# LORATA.net
KiCad netlist of a schematic drawn in Altium Designer
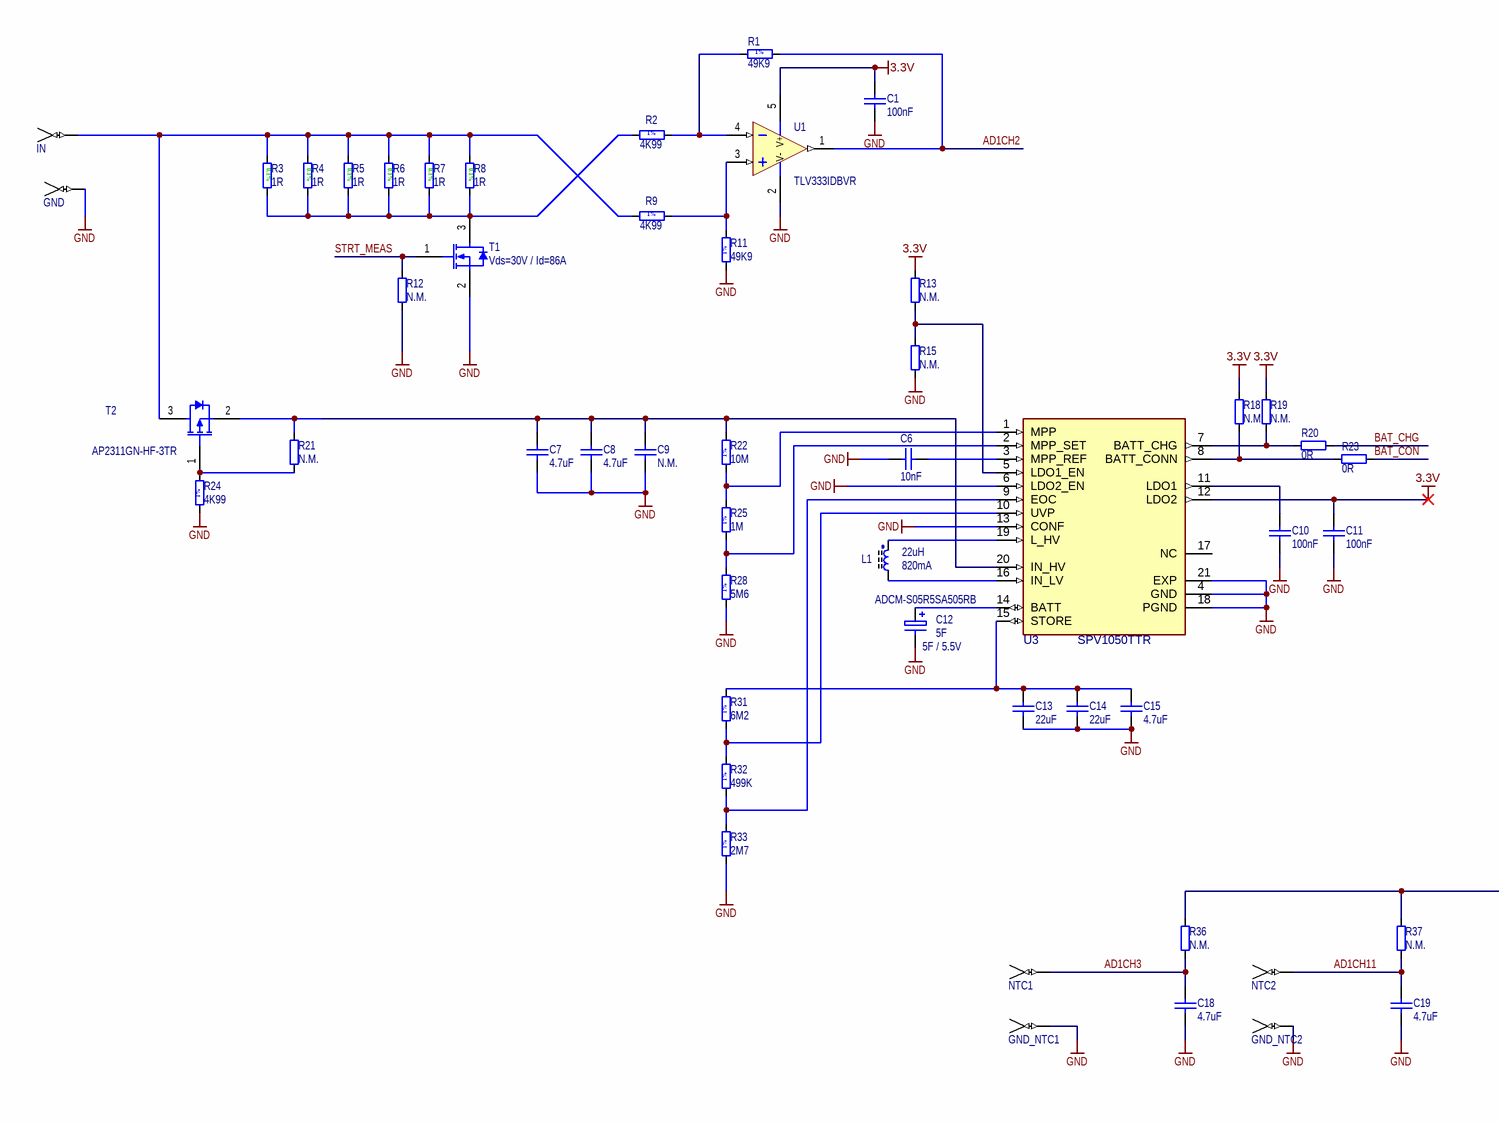
[diagram p0: LORATA.SchDoc, left]
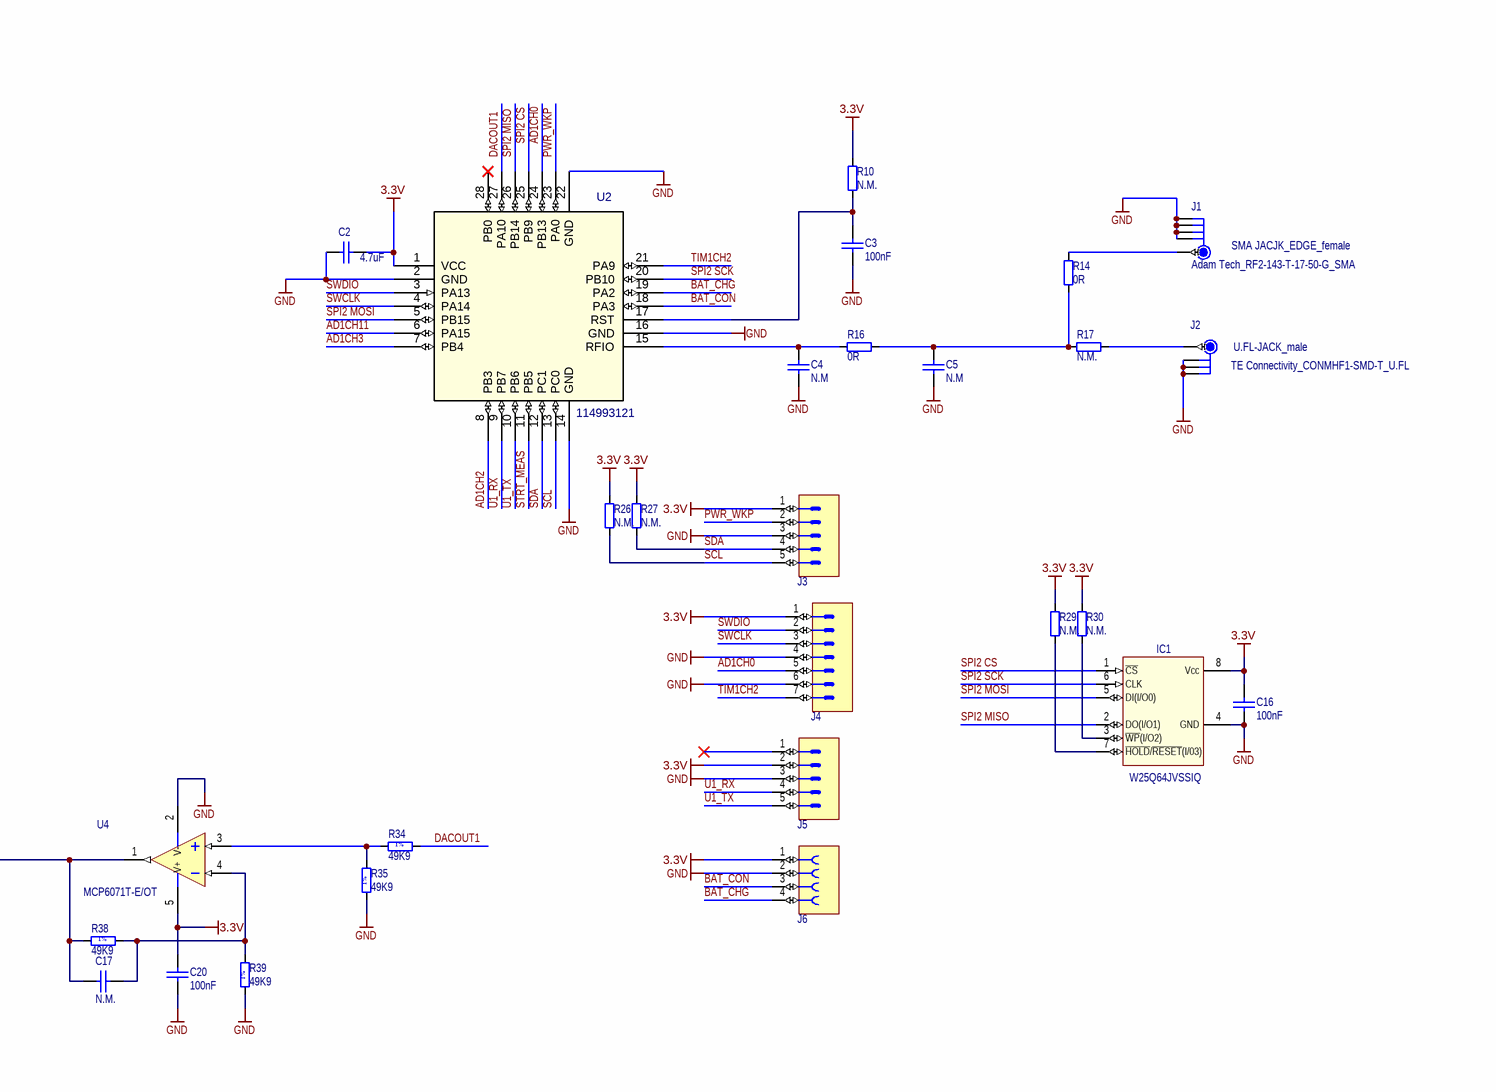
[diagram p1: LORATA.SchDoc, right]

(export (version "E")
  (design (tool "Eeschema 10.0.6"))
  (components
    (comp (ref "C1")
      (value "100nF")
      (footprint "CAPC1608N")
      (description "Non-polarised capacitor")
      (fields
        (field (name "PART NUMBER") "CC0603_100NF_50V_10%_X7R")
        (field (name "VOLTAGE") "50V")
        (field (name "AUTHOR") "V.Shishkov")
      )
      (libsource (lib "IDT_BASE") (part "C"))
    )
    (comp (ref "C2")
      (value "4.7uF")
      (footprint "CAPC3216N")
      (description "Non-polarised capacitor")
      (fields
        (field (name "PART NUMBER") "CC1206_4.7UF_50V_10%_X7R")
        (field (name "VOLTAGE") "50V")
        (field (name "AUTHOR") "V.Shishkov")
      )
      (libsource (lib "IDT_BASE") (part "C"))
    )
    (comp (ref "C3")
      (value "100nF")
      (footprint "CAPC1608N")
      (description "Non-polarised capacitor")
      (fields
        (field (name "PART NUMBER") "CC0603_100NF_50V_10%_X7R")
        (field (name "VOLTAGE") "50V")
        (field (name "AUTHOR") "V.Shishkov")
      )
      (libsource (lib "IDT_BASE") (part "C"))
    )
    (comp (ref "C4")
      (value "N.M")
      (footprint "CAPC1608N")
      (description "Non-polarised capacitor")
      (fields
        (field (name "PART NUMBER") "CC0603_NO-VALUE")
        (field (name "MANUFACTURER") "GENERIC")
        (field (name "AUTHOR") "L.K")
      )
      (libsource (lib "IDT_BASE") (part "C"))
    )
    (comp (ref "C5")
      (value "N.M")
      (footprint "CAPC1608N")
      (description "Non-polarised capacitor")
      (fields
        (field (name "PART NUMBER") "CC0603_NO-VALUE")
        (field (name "MANUFACTURER") "GENERIC")
        (field (name "AUTHOR") "L.K")
      )
      (libsource (lib "IDT_BASE") (part "C"))
    )
    (comp (ref "C6")
      (value "10nF")
      (footprint "CAPC1608N")
      (description "Non-polarised capacitor")
      (fields
        (field (name "PART NUMBER") "CC0603_10NF_50V_10%_X7R")
        (field (name "VOLTAGE") "50V")
        (field (name "AUTHOR") "V.Shishkov")
      )
      (libsource (lib "IDT_BASE") (part "C"))
    )
    (comp (ref "C7")
      (value "4.7uF")
      (footprint "CAPC3216N")
      (description "Non-polarised capacitor")
      (fields
        (field (name "PART NUMBER") "CC1206_4.7UF_50V_10%_X7R")
        (field (name "VOLTAGE") "50V")
        (field (name "AUTHOR") "V.Shishkov")
      )
      (libsource (lib "IDT_BASE") (part "C"))
    )
    (comp (ref "C8")
      (value "4.7uF")
      (footprint "CAPC3216N")
      (description "Non-polarised capacitor")
      (fields
        (field (name "PART NUMBER") "CC1206_4.7UF_50V_10%_X7R")
        (field (name "VOLTAGE") "50V")
        (field (name "AUTHOR") "V.Shishkov")
      )
      (libsource (lib "IDT_BASE") (part "C"))
    )
    (comp (ref "C9")
      (value "N.M.")
      (footprint "CAPC2012N")
      (description "Non-polarised capacitor")
      (fields
        (field (name "PART NUMBER") "CC0805_NO-VALUE")
        (field (name "MANUFACTURER") "Undefined")
        (field (name "AUTHOR") "V.Shishkov")
      )
      (libsource (lib "IDT_BASE") (part "C"))
    )
    (comp (ref "C10")
      (value "100nF")
      (footprint "CAPC1608N")
      (description "Non-polarised capacitor")
      (fields
        (field (name "PART NUMBER") "CC0603_100NF_50V_10%_X7R")
        (field (name "VOLTAGE") "50V")
        (field (name "AUTHOR") "V.Shishkov")
      )
      (libsource (lib "IDT_BASE") (part "C"))
    )
    (comp (ref "C11")
      (value "100nF")
      (footprint "CAPC1608N")
      (description "Non-polarised capacitor")
      (fields
        (field (name "PART NUMBER") "CC0603_100NF_50V_10%_X7R")
        (field (name "VOLTAGE") "50V")
        (field (name "AUTHOR") "V.Shishkov")
      )
      (libsource (lib "IDT_BASE") (part "C"))
    )
    (comp (ref "C12")
      (value "5F")
      (footprint "CAPR1530x1050X2050X2800")
      (description "Polarised capacitor")
      (fields
        (field (name "PART NUMBER") "CAER_5F_5.5V_0%+30%")
        (field (name "COMMENT_RATINGS") "5F / 5.5V")
        (field (name "VOLTAGE") "5.5V")
        (field (name "MANUFACTURER PART NUMBER") "ADCM-S05R5SA505RB")
        (field (name "AUTHOR") "L.Karamfilov")
      )
      (libsource (lib "IDT_BASE") (part "C+"))
    )
    (comp (ref "C13")
      (value "22uF")
      (footprint "CAPC3225N")
      (description "Non-polarised capacitor")
      (fields
        (field (name "PART NUMBER") "CC1210_22UF_16V_10%_X7R")
        (field (name "VOLTAGE") "16V")
        (field (name "AUTHOR") "V.Shishkov")
      )
      (libsource (lib "IDT_BASE") (part "C"))
    )
    (comp (ref "C14")
      (value "22uF")
      (footprint "CAPC3225N")
      (description "Non-polarised capacitor")
      (fields
        (field (name "PART NUMBER") "CC1210_22UF_16V_10%_X7R")
        (field (name "VOLTAGE") "16V")
        (field (name "AUTHOR") "V.Shishkov")
      )
      (libsource (lib "IDT_BASE") (part "C"))
    )
    (comp (ref "C15")
      (value "4.7uF")
      (footprint "CAPC3216N")
      (description "Non-polarised capacitor")
      (fields
        (field (name "PART NUMBER") "CC1206_4.7UF_50V_10%_X7R")
        (field (name "VOLTAGE") "50V")
        (field (name "AUTHOR") "V.Shishkov")
      )
      (libsource (lib "IDT_BASE") (part "C"))
    )
    (comp (ref "C16")
      (value "100nF")
      (footprint "CAPC1608N")
      (description "Non-polarised capacitor")
      (fields
        (field (name "PART NUMBER") "CC0603_100NF_50V_10%_X7R")
        (field (name "VOLTAGE") "50V")
        (field (name "AUTHOR") "V.Shishkov")
      )
      (libsource (lib "IDT_BASE") (part "C"))
    )
    (comp (ref "C17")
      (value "N.M.")
      (footprint "CAPC2012N")
      (description "Non-polarised capacitor")
      (fields
        (field (name "PART NUMBER") "CC0805_NO-VALUE")
        (field (name "MANUFACTURER") "Undefined")
        (field (name "AUTHOR") "V.Shishkov")
      )
      (libsource (lib "IDT_BASE") (part "C"))
    )
    (comp (ref "C18")
      (value "4.7uF")
      (footprint "CAPC3216N")
      (description "Non-polarised capacitor")
      (fields
        (field (name "PART NUMBER") "CC1206_4.7UF_50V_10%_X7R")
        (field (name "VOLTAGE") "50V")
        (field (name "AUTHOR") "V.Shishkov")
      )
      (libsource (lib "IDT_BASE") (part "C"))
    )
    (comp (ref "C19")
      (value "4.7uF")
      (footprint "CAPC3216N")
      (description "Non-polarised capacitor")
      (fields
        (field (name "PART NUMBER") "CC1206_4.7UF_50V_10%_X7R")
        (field (name "VOLTAGE") "50V")
        (field (name "AUTHOR") "V.Shishkov")
      )
      (libsource (lib "IDT_BASE") (part "C"))
    )
    (comp (ref "C20")
      (value "100nF")
      (footprint "CAPC1608N")
      (description "Non-polarised capacitor")
      (fields
        (field (name "PART NUMBER") "CC0603_100NF_50V_10%_X7R")
        (field (name "VOLTAGE") "50V")
        (field (name "AUTHOR") "V.Shishkov")
      )
      (libsource (lib "IDT_BASE") (part "C"))
    )
    (comp (ref "GND")
      (value "~")
      (footprint "PIN_1.5MM_HOLE")
      (description "Through Hole Pad")
      (fields (field (name "PART NUMBER") "PAD_1.5mm_HOLE") (field (name "AUTHOR") "L.K"))
      (libsource (lib "IDT_BASE") (part "Through Hole Pad_1"))
    )
    (comp (ref "GND_NTC1")
      (value "~")
      (footprint "PIN_1.5MM_HOLE")
      (description "Through Hole Pad")
      (fields (field (name "PART NUMBER") "PAD_1.5mm_HOLE") (field (name "AUTHOR") "L.K"))
      (libsource (lib "IDT_BASE") (part "Through Hole Pad_1"))
    )
    (comp (ref "GND_NTC2")
      (value "~")
      (footprint "PIN_1.5MM_HOLE")
      (description "Through Hole Pad")
      (fields (field (name "PART NUMBER") "PAD_1.5mm_HOLE") (field (name "AUTHOR") "L.K"))
      (libsource (lib "IDT_BASE") (part "Through Hole Pad_1"))
    )
    (comp (ref "IC1")
      (value "W25Q64JVSSIQ")
      (footprint "SOIC127P600-8N")
      (description "FLASH - NOR Memory IC 64Mbit SPI - Quad I/O 133 MHz 8-SOIC")
      (fields (field (name "MANUFACTURER") "Winbond Electronics") (field (name "AUTHOR") "L.Karamfilov"))
      (libsource (lib "IDT_BASE") (part "W25Q64JVSSIQ"))
    )
    (comp (ref "IN")
      (value "~")
      (footprint "PIN_1.5MM_HOLE")
      (description "Through Hole Pad")
      (fields (field (name "PART NUMBER") "PAD_1.5mm_HOLE") (field (name "AUTHOR") "L.K"))
      (libsource (lib "IDT_BASE") (part "Through Hole Pad_1"))
    )
    (comp (ref "J1")
      (value "SMA JACJK_EDGE_female")
      (footprint "Adam Tech_RF2-143-T-17-50-G")
      (fields
        (field (name "PART NUMBER") "Adam Tech_RF2-143-T-17-50-G_SMA")
        (field (name "MANUFACTURER") "Adam Tech")
        (field (name "MANUFACTURER PART NUMBER") "RF2-143-T-17-50-G")
        (field (name "AUTHOR") "L.KARAMFILOV")
      )
      (libsource (lib "IDT_BASE") (part "Coax_SMD_1+4Shield"))
    )
    (comp (ref "J2")
      (value "U.FL-JACK_male")
      (footprint "LINX_CONMHF1-SMD-T")
      (fields
        (field (name "PART NUMBER") "TE Connectivity_CONMHF1-SMD-T_U.FL")
        (field (name "MANUFACTURER") "TE Connectivity Linx")
        (field (name "MANUFACTURER PART NUMBER") "CONMHF1-SMD-T")
        (field (name "AUTHOR") "L.KARAMFILOV")
      )
      (libsource (lib "IDT_BASE") (part "Coax_SMD_1+3Shield"))
    )
    (comp (ref "J3")
      (value "HEADER 1X5")
      (footprint "HDR1X5")
      (description "Connector 5 Male")
      (fields
        (field (name "PART NUMBER") "HEADER 1 X 5_2.54MM")
        (field (name "MANUFACTURER PART NUMBER") "DO NOT MOUNT")
        (field (name "AUTHOR") "L.K")
      )
      (libsource (lib "IDT_BASE") (part "Connector 5 Male"))
    )
    (comp (ref "J4")
      (value "HEADER 1X7")
      (footprint "HDR1X7")
      (description "Connector 7 Male")
      (fields
        (field (name "PART NUMBER") "HEADER 1 X 7_2.54MM")
        (field (name "MANUFACTURER PART NUMBER") "DO NOT MOUNT")
        (field (name "AUTHOR") "L.K")
      )
      (libsource (lib "IDT_BASE") (part "Connector 7 Male"))
    )
    (comp (ref "J5")
      (value "HEADER 1X5")
      (footprint "HDR1X5")
      (description "Connector 5 Male")
      (fields
        (field (name "PART NUMBER") "HEADER 1 X 5_2.54MM")
        (field (name "MANUFACTURER PART NUMBER") "DO NOT MOUNT")
        (field (name "AUTHOR") "L.K")
      )
      (libsource (lib "IDT_BASE") (part "Connector 5 Male"))
    )
    (comp (ref "J6")
      (value "Header Female")
      (footprint "HARWIN_M20-7820442")
      (description "Connector 4 Female")
      (fields
        (field (name "PART NUMBER") "M20-7820442")
        (field (name "MANUFACTURER") "HARWIN")
        (field (name "AUTHOR") "L.KARAMFILOV")
      )
      (libsource (lib "IDT_BASE") (part "Connector 4 Female"))
    )
    (comp (ref "L1")
      (value "22uH")
      (footprint "IND_Taiyo_NRS5024")
      (description "Inductor")
      (fields
        (field (name "PART NUMBER") "IND_22UH_20%_Taiyo-Yuden_NRS5024T220MMGJV")
        (field (name "POWER") "820mA")
        (field (name "TOLERANCE") "±20%")
        (field (name "AUTHOR") "L.KARAMFILOV")
      )
      (libsource (lib "IDT_BASE") (part "Inductor_Shield"))
    )
    (comp (ref "NTC1")
      (value "~")
      (footprint "PIN_1.5MM_HOLE")
      (description "Through Hole Pad")
      (fields (field (name "PART NUMBER") "PAD_1.5mm_HOLE") (field (name "AUTHOR") "L.K"))
      (libsource (lib "IDT_BASE") (part "Through Hole Pad_1"))
    )
    (comp (ref "NTC2")
      (value "~")
      (footprint "PIN_1.5MM_HOLE")
      (description "Through Hole Pad")
      (fields (field (name "PART NUMBER") "PAD_1.5mm_HOLE") (field (name "AUTHOR") "L.K"))
      (libsource (lib "IDT_BASE") (part "Through Hole Pad_1"))
    )
    (comp (ref "R1")
      (value "49K9")
      (footprint "RESC1608N(0603)")
      (description "Resistor-1%")
      (fields
        (field (name "PART NUMBER") "R0603_49K9_1%_0.1W_100PPM")
        (field (name "POWER") "0.1W")
        (field (name "AUTHOR") "L.KARAMFILOV")
      )
      (libsource (lib "") (part "R- 1%_2"))
    )
    (comp (ref "R2")
      (value "4K99")
      (footprint "RESC2012N(0805)")
      (description "Resistor-1%")
      (fields
        (field (name "PART NUMBER") "R0805_4K99_1%_0.125W_100PPM")
        (field (name "POWER") "0.125W")
        (field (name "AUTHOR") "L.KARAMFILOV")
      )
      (libsource (lib "") (part "R- 1%_2"))
    )
    (comp (ref "R3")
      (value "1R")
      (footprint "RESC3216N(1206)")
      (description "Resistor-0.1%")
      (fields
        (field (name "PART NUMBER") "R1206_1R_0.5%_0.52W_25PPM")
        (field (name "POWER") "0.25W")
        (field (name "AUTHOR") "L.KARAMFILOV")
      )
      (libsource (lib "IDT_BASE") (part "R-0.1%"))
    )
    (comp (ref "R4")
      (value "1R")
      (footprint "RESC3216N(1206)")
      (description "Resistor-0.1%")
      (fields
        (field (name "PART NUMBER") "R1206_1R_0.5%_0.52W_25PPM")
        (field (name "POWER") "0.25W")
        (field (name "AUTHOR") "L.KARAMFILOV")
      )
      (libsource (lib "IDT_BASE") (part "R-0.1%"))
    )
    (comp (ref "R5")
      (value "1R")
      (footprint "RESC3216N(1206)")
      (description "Resistor-0.1%")
      (fields
        (field (name "PART NUMBER") "R1206_1R_0.5%_0.52W_25PPM")
        (field (name "POWER") "0.25W")
        (field (name "AUTHOR") "L.KARAMFILOV")
      )
      (libsource (lib "IDT_BASE") (part "R-0.1%"))
    )
    (comp (ref "R6")
      (value "1R")
      (footprint "RESC3216N(1206)")
      (description "Resistor-0.1%")
      (fields
        (field (name "PART NUMBER") "R1206_1R_0.5%_0.52W_25PPM")
        (field (name "POWER") "0.25W")
        (field (name "AUTHOR") "L.KARAMFILOV")
      )
      (libsource (lib "IDT_BASE") (part "R-0.1%"))
    )
    (comp (ref "R7")
      (value "1R")
      (footprint "RESC3216N(1206)")
      (description "Resistor-0.1%")
      (fields
        (field (name "PART NUMBER") "R1206_1R_0.5%_0.52W_25PPM")
        (field (name "POWER") "0.25W")
        (field (name "AUTHOR") "L.KARAMFILOV")
      )
      (libsource (lib "IDT_BASE") (part "R-0.1%"))
    )
    (comp (ref "R8")
      (value "1R")
      (footprint "RESC3216N(1206)")
      (description "Resistor-0.1%")
      (fields
        (field (name "PART NUMBER") "R1206_1R_0.5%_0.52W_25PPM")
        (field (name "POWER") "0.25W")
        (field (name "AUTHOR") "L.KARAMFILOV")
      )
      (libsource (lib "IDT_BASE") (part "R-0.1%"))
    )
    (comp (ref "R9")
      (value "4K99")
      (footprint "RESC2012N(0805)")
      (description "Resistor-1%")
      (fields
        (field (name "PART NUMBER") "R0805_4K99_1%_0.125W_100PPM")
        (field (name "POWER") "0.125W")
        (field (name "AUTHOR") "L.KARAMFILOV")
      )
      (libsource (lib "") (part "R- 1%_2"))
    )
    (comp (ref "R10")
      (value "N.M.")
      (footprint "RESC1608N(0603)")
      (description "Resistor")
      (fields
        (field (name "PART NUMBER") "R0603_NO-VALUE")
        (field (name "MANUFACTURER") "Undefined")
        (field (name "AUTHOR") "L.KARAMFILOV")
      )
      (libsource (lib "") (part "R_1"))
    )
    (comp (ref "R11")
      (value "49K9")
      (footprint "RESC1608N(0603)")
      (description "Resistor-1%")
      (fields
        (field (name "PART NUMBER") "R0603_49K9_1%_0.1W_100PPM")
        (field (name "POWER") "0.1W")
        (field (name "AUTHOR") "L.KARAMFILOV")
      )
      (libsource (lib "IDT_BASE") (part "R- 1%"))
    )
    (comp (ref "R12")
      (value "N.M.")
      (footprint "RESC1608N(0603)")
      (description "Resistor")
      (fields
        (field (name "PART NUMBER") "R0603_NO-VALUE")
        (field (name "MANUFACTURER") "Undefined")
        (field (name "AUTHOR") "L.KARAMFILOV")
      )
      (libsource (lib "") (part "R_1"))
    )
    (comp (ref "R13")
      (value "N.M.")
      (footprint "RESC1608N(0603)")
      (description "Resistor")
      (fields
        (field (name "PART NUMBER") "R0603_NO-VALUE")
        (field (name "MANUFACTURER") "Undefined")
        (field (name "AUTHOR") "L.KARAMFILOV")
      )
      (libsource (lib "") (part "R_1"))
    )
    (comp (ref "R14")
      (value "0R")
      (footprint "RESC1608N(0603)")
      (description "Resistor")
      (fields
        (field (name "PART NUMBER") "R0603_0R_JUMPER")
        (field (name "MANUFACTURER") "GENERIC")
        (field (name "AUTHOR") "L.KARAMFILOV")
      )
      (libsource (lib "") (part "R_1"))
    )
    (comp (ref "R15")
      (value "N.M.")
      (footprint "RESC1608N(0603)")
      (description "Resistor")
      (fields
        (field (name "PART NUMBER") "R0603_NO-VALUE")
        (field (name "MANUFACTURER") "Undefined")
        (field (name "AUTHOR") "L.KARAMFILOV")
      )
      (libsource (lib "") (part "R_1"))
    )
    (comp (ref "R16")
      (value "0R")
      (footprint "RESC1608N(0603)")
      (description "Resistor")
      (fields
        (field (name "PART NUMBER") "R0603_0R_JUMPER")
        (field (name "MANUFACTURER") "GENERIC")
        (field (name "AUTHOR") "L.KARAMFILOV")
      )
      (libsource (lib "IDT_BASE") (part "R"))
    )
    (comp (ref "R17")
      (value "N.M.")
      (footprint "RESC1608N(0603)")
      (description "Resistor")
      (fields
        (field (name "PART NUMBER") "R0603_NO-VALUE")
        (field (name "MANUFACTURER") "Undefined")
        (field (name "AUTHOR") "L.KARAMFILOV")
      )
      (libsource (lib "IDT_BASE") (part "R"))
    )
    (comp (ref "R18")
      (value "N.M.")
      (footprint "RESC1608N(0603)")
      (description "Resistor")
      (fields
        (field (name "PART NUMBER") "R0603_NO-VALUE")
        (field (name "MANUFACTURER") "Undefined")
        (field (name "AUTHOR") "L.KARAMFILOV")
      )
      (libsource (lib "") (part "R_1"))
    )
    (comp (ref "R19")
      (value "N.M.")
      (footprint "RESC1608N(0603)")
      (description "Resistor")
      (fields
        (field (name "PART NUMBER") "R0603_NO-VALUE")
        (field (name "MANUFACTURER") "Undefined")
        (field (name "AUTHOR") "L.KARAMFILOV")
      )
      (libsource (lib "") (part "R_1"))
    )
    (comp (ref "R20")
      (value "0R")
      (footprint "RESC1608N(0603)")
      (description "Resistor")
      (fields
        (field (name "PART NUMBER") "R0603_0R_JUMPER")
        (field (name "MANUFACTURER") "GENERIC")
        (field (name "AUTHOR") "L.KARAMFILOV")
      )
      (libsource (lib "IDT_BASE") (part "R"))
    )
    (comp (ref "R21")
      (value "N.M.")
      (footprint "RESC1608N(0603)")
      (description "Resistor")
      (fields
        (field (name "PART NUMBER") "R0603_NO-VALUE")
        (field (name "MANUFACTURER") "Undefined")
        (field (name "AUTHOR") "L.KARAMFILOV")
      )
      (libsource (lib "") (part "R_1"))
    )
    (comp (ref "R22")
      (value "10M")
      (footprint "RESC2012N(0805)")
      (description "Resistor-1%")
      (fields
        (field (name "PART NUMBER") "R0805_10M_1%_0.125W_100PPM")
        (field (name "POWER") "0.125W")
        (field (name "AUTHOR") "L.KARAMFILOV")
      )
      (libsource (lib "IDT_BASE") (part "R- 1%"))
    )
    (comp (ref "R23")
      (value "0R")
      (footprint "RESC1608N(0603)")
      (description "Resistor")
      (fields
        (field (name "PART NUMBER") "R0603_0R_JUMPER")
        (field (name "MANUFACTURER") "GENERIC")
        (field (name "AUTHOR") "L.KARAMFILOV")
      )
      (libsource (lib "IDT_BASE") (part "R"))
    )
    (comp (ref "R24")
      (value "4K99")
      (footprint "RESC2012N(0805)")
      (description "Resistor-1%")
      (fields
        (field (name "PART NUMBER") "R0805_4K99_1%_0.125W_100PPM")
        (field (name "POWER") "0.125W")
        (field (name "AUTHOR") "L.KARAMFILOV")
      )
      (libsource (lib "IDT_BASE") (part "R- 1%"))
    )
    (comp (ref "R25")
      (value "1M")
      (footprint "RESC2012N(0805)")
      (description "Resistor-1%")
      (fields
        (field (name "PART NUMBER") "R0805_1M_1%_0.125W_100PPM")
        (field (name "POWER") "0.125W")
        (field (name "AUTHOR") "L.KARAMFILOV")
      )
      (libsource (lib "IDT_BASE") (part "R- 1%"))
    )
    (comp (ref "R26")
      (value "N.M.")
      (footprint "RESC1608N(0603)")
      (description "Resistor")
      (fields
        (field (name "PART NUMBER") "R0603_NO-VALUE")
        (field (name "MANUFACTURER") "Undefined")
        (field (name "AUTHOR") "L.KARAMFILOV")
      )
      (libsource (lib "") (part "R_1"))
    )
    (comp (ref "R27")
      (value "N.M.")
      (footprint "RESC1608N(0603)")
      (description "Resistor")
      (fields
        (field (name "PART NUMBER") "R0603_NO-VALUE")
        (field (name "MANUFACTURER") "Undefined")
        (field (name "AUTHOR") "L.KARAMFILOV")
      )
      (libsource (lib "") (part "R_1"))
    )
    (comp (ref "R28")
      (value "5M6")
      (footprint "RESC2012N(0805)")
      (description "Resistor-1%")
      (fields
        (field (name "PART NUMBER") "R0805_5M6_1%_0.125W_100PPM")
        (field (name "POWER") "0.125W")
        (field (name "AUTHOR") "L.KARAMFILOV")
      )
      (libsource (lib "IDT_BASE") (part "R- 1%"))
    )
    (comp (ref "R29")
      (value "N.M.")
      (footprint "RESC1608N(0603)")
      (description "Resistor")
      (fields
        (field (name "PART NUMBER") "R0603_NO-VALUE")
        (field (name "MANUFACTURER") "Undefined")
        (field (name "AUTHOR") "L.KARAMFILOV")
      )
      (libsource (lib "") (part "R_1"))
    )
    (comp (ref "R30")
      (value "N.M.")
      (footprint "RESC1608N(0603)")
      (description "Resistor")
      (fields
        (field (name "PART NUMBER") "R0603_NO-VALUE")
        (field (name "MANUFACTURER") "Undefined")
        (field (name "AUTHOR") "L.KARAMFILOV")
      )
      (libsource (lib "") (part "R_1"))
    )
    (comp (ref "R31")
      (value "6M2")
      (footprint "RESC2012N(0805)")
      (description "Resistor-1%")
      (fields
        (field (name "PART NUMBER") "R0805_6M2_1%_0.125W_100PPM")
        (field (name "POWER") "0.125W")
        (field (name "AUTHOR") "L.KARAMFILOV")
      )
      (libsource (lib "IDT_BASE") (part "R- 1%"))
    )
    (comp (ref "R32")
      (value "499K")
      (footprint "RESC2012N(0805)")
      (description "Resistor-1%")
      (fields
        (field (name "PART NUMBER") "R0805_499K_1%_0.125W_100PPM")
        (field (name "POWER") "0.125W")
        (field (name "AUTHOR") "L.KARAMFILOV")
      )
      (libsource (lib "IDT_BASE") (part "R- 1%"))
    )
    (comp (ref "R33")
      (value "2M7")
      (footprint "RESC2012N(0805)")
      (description "Resistor-1%")
      (fields
        (field (name "PART NUMBER") "R0805_2M7_1%_0.125W_100PPM")
        (field (name "POWER") "0.125W")
        (field (name "AUTHOR") "L.KARAMFILOV")
      )
      (libsource (lib "IDT_BASE") (part "R- 1%"))
    )
    (comp (ref "R34")
      (value "49K9")
      (footprint "RESC1608N(0603)")
      (description "Resistor-1%")
      (fields
        (field (name "PART NUMBER") "R0603_49K9_1%_0.1W_100PPM")
        (field (name "POWER") "0.1W")
        (field (name "AUTHOR") "L.KARAMFILOV")
      )
      (libsource (lib "") (part "R- 1%_2"))
    )
    (comp (ref "R35")
      (value "49K9")
      (footprint "RESC1608N(0603)")
      (description "Resistor-1%")
      (fields
        (field (name "PART NUMBER") "R0603_49K9_1%_0.1W_100PPM")
        (field (name "POWER") "0.1W")
        (field (name "AUTHOR") "L.KARAMFILOV")
      )
      (libsource (lib "IDT_BASE") (part "R- 1%"))
    )
    (comp (ref "R36")
      (value "N.M.")
      (footprint "RESC1608N(0603)")
      (description "Resistor")
      (fields
        (field (name "PART NUMBER") "R0603_NO-VALUE")
        (field (name "MANUFACTURER") "Undefined")
        (field (name "AUTHOR") "L.KARAMFILOV")
      )
      (libsource (lib "") (part "R_1"))
    )
    (comp (ref "R37")
      (value "N.M.")
      (footprint "RESC1608N(0603)")
      (description "Resistor")
      (fields
        (field (name "PART NUMBER") "R0603_NO-VALUE")
        (field (name "MANUFACTURER") "Undefined")
        (field (name "AUTHOR") "L.KARAMFILOV")
      )
      (libsource (lib "") (part "R_1"))
    )
    (comp (ref "R38")
      (value "49K9")
      (footprint "RESC1608N(0603)")
      (description "Resistor-1%")
      (fields
        (field (name "PART NUMBER") "R0603_49K9_1%_0.1W_100PPM")
        (field (name "POWER") "0.1W")
        (field (name "AUTHOR") "L.KARAMFILOV")
      )
      (libsource (lib "") (part "R- 1%_1"))
    )
    (comp (ref "R39")
      (value "49K9")
      (footprint "RESC1608N(0603)")
      (description "Resistor-1%")
      (fields
        (field (name "PART NUMBER") "R0603_49K9_1%_0.1W_100PPM")
        (field (name "POWER") "0.1W")
        (field (name "AUTHOR") "L.KARAMFILOV")
      )
      (libsource (lib "IDT_BASE") (part "R- 1%"))
    )
    (comp (ref "T1")
      (value "IRLR8726PBF")
      (footprint "TO228P991X239-3N-R546X521")
      (description "N-channel FET transistor in SOT-23")
      (fields
        (field (name "COMMENT_RATINGS") "Vds=30V / Id=86A")
        (field (name "MANUFACTURER") "INFINEON TECHNOLOGIES")
        (field (name "AUTHOR") "L.Karmafilov")
      )
      (libsource (lib "IDT_BASE") (part "FET-N_SMD"))
    )
    (comp (ref "T2")
      (value "AP2311GN-HF-3TR")
      (footprint "SOT95P240X130-3N")
      (description "P-channel FET transistor in SOT-23")
      (fields
        (field (name "MANUFACTURER") "ADVANCED POWER ELECTR. CO")
        (field (name "AUTHOR") "L.Karmafilov")
      )
      (libsource (lib "IDT_BASE") (part "FET-P_SMD"))
    )
    (comp (ref "U1")
      (value "TLV333IDBVR")
      (footprint "SOT95P280X145-5N")
      (description "Single Op Amp in SOT23/5")
      (fields (field (name "MANUFACTURER") "TEXAS INSTRUMENTS") (field (name "AUTHOR") "L.Karamfilov"))
      (libsource (lib "IDT_BASE") (part "OpAmp_S"))
    )
    (comp (ref "U2")
      (value "114993121")
      (footprint "QFN_90687_SEE-L")
      (description "WIO-E5-LE WIRELESS MODULE (TAPE)")
      (fields
        (field (name "PART NUMBER") "114993121_RF_SEED")
        (field (name "MANUFACTURER") "Seeed Technology Co., Ltd")
        (field (name "AUTHOR") "L.Karamfilov")
      )
      (libsource (lib "IDT_BASE") (part "RF_RXTX_114993121"))
    )
    (comp (ref "U3")
      (value "SPV1050TTR")
      (footprint "QFN40P300X300X100-21N")
      (description "Charger IC Multi-Chemistry 20-VFQFPN (3x3)")
      (fields (field (name "MF") "STMicroelectronics") (field (name "AUTHOR") "L.Karamfilov"))
      (libsource (lib "IDT_BASE") (part "SPV1050TTR"))
    )
    (comp (ref "U4")
      (value "MCP6071T-E/OT")
      (footprint "SOT95P280X145-5N")
      (description "Single Op Amp in SOT23/5")
      (fields (field (name "MANUFACTURER") "Analog Devices") (field (name "AUTHOR") "L.Karamfilov"))
      (libsource (lib "IDT_BASE") (part "OpAmp_S"))
    )
  )
  (nets
    (net (code "1") (name "/AD1CH0") (class "Default")
      (node (ref "J4") (pin "5") (pinfunction "5_5") (pintype "bidirectional"))
      (node (ref "U2") (pin "24") (pinfunction "PB13_24") (pintype "bidirectional"))
    )
    (net (code "2") (name "/AD1CH2") (class "Default")
      (node (ref "R1") (pin "2") (pinfunction "2_2") (pintype "passive"))
      (node (ref "U1") (pin "1") (pinfunction "OUT_1") (pintype "output"))
      (node (ref "U2") (pin "8") (pinfunction "PB3_8") (pintype "bidirectional"))
    )
    (net (code "3") (name "/AD1CH3") (class "Default")
      (node (ref "C18") (pin "2") (pinfunction "2_2") (pintype "passive"))
      (node (ref "NTC1") (pin "1") (pinfunction "1_1") (pintype "bidirectional"))
      (node (ref "R36") (pin "1") (pinfunction "1_1") (pintype "passive"))
      (node (ref "U2") (pin "7") (pinfunction "PB4_7") (pintype "bidirectional"))
    )
    (net (code "4") (name "/AD1CH11") (class "Default")
      (node (ref "C19") (pin "2") (pinfunction "2_2") (pintype "passive"))
      (node (ref "NTC2") (pin "1") (pinfunction "1_1") (pintype "bidirectional"))
      (node (ref "R37") (pin "1") (pinfunction "1_1") (pintype "passive"))
      (node (ref "U2") (pin "6") (pinfunction "PA15_6") (pintype "bidirectional"))
    )
    (net (code "5") (name "/BAT_CHG") (class "Default")
      (node (ref "J6") (pin "4") (pinfunction "4_4") (pintype "bidirectional"))
      (node (ref "R20") (pin "2") (pinfunction "2_2") (pintype "passive"))
      (node (ref "U2") (pin "19") (pinfunction "PA2_19") (pintype "bidirectional"))
    )
    (net (code "6") (name "/BAT_CON") (class "Default")
      (node (ref "J6") (pin "3") (pinfunction "3_3") (pintype "bidirectional"))
      (node (ref "R23") (pin "2") (pinfunction "2_2") (pintype "passive"))
      (node (ref "U2") (pin "18") (pinfunction "PA3_18") (pintype "bidirectional"))
    )
    (net (code "7") (name "/DACOUT1") (class "Default")
      (node (ref "R34") (pin "2") (pinfunction "2_2") (pintype "passive"))
      (node (ref "U2") (pin "27") (pinfunction "PA10_27") (pintype "bidirectional"))
    )
    (net (code "8") (name "/PWR_WKP") (class "Default")
      (node (ref "J3") (pin "2") (pinfunction "2_2") (pintype "bidirectional"))
      (node (ref "U2") (pin "23") (pinfunction "PA0_23") (pintype "bidirectional"))
    )
    (net (code "9") (name "/SCL") (class "Default")
      (node (ref "J3") (pin "5") (pinfunction "5_5") (pintype "bidirectional"))
      (node (ref "R26") (pin "1") (pinfunction "1_1") (pintype "passive"))
      (node (ref "U2") (pin "13") (pinfunction "PC0_13") (pintype "bidirectional"))
    )
    (net (code "10") (name "/SDA") (class "Default")
      (node (ref "J3") (pin "4") (pinfunction "4_4") (pintype "bidirectional"))
      (node (ref "R27") (pin "1") (pinfunction "1_1") (pintype "passive"))
      (node (ref "U2") (pin "12") (pinfunction "PC1_12") (pintype "bidirectional"))
    )
    (net (code "11") (name "/SPI2 CS") (class "Default")
      (node (ref "IC1") (pin "1") (pinfunction "~{CS}_1") (pintype "input"))
      (node (ref "U2") (pin "25") (pinfunction "PB9_25") (pintype "bidirectional"))
    )
    (net (code "12") (name "/SPI2 MISO") (class "Default")
      (node (ref "IC1") (pin "2") (pinfunction "DO(I/O1)_2") (pintype "bidirectional"))
      (node (ref "U2") (pin "26") (pinfunction "PB14_26") (pintype "bidirectional"))
    )
    (net (code "13") (name "/SPI2 MOSI") (class "Default")
      (node (ref "IC1") (pin "5") (pinfunction "DI(I/O0)_5") (pintype "bidirectional"))
      (node (ref "U2") (pin "5") (pinfunction "PB15_5") (pintype "bidirectional"))
    )
    (net (code "14") (name "/SPI2 SCK") (class "Default")
      (node (ref "IC1") (pin "6") (pinfunction "CLK_6") (pintype "input"))
      (node (ref "U2") (pin "20") (pinfunction "PB10_20") (pintype "bidirectional"))
    )
    (net (code "15") (name "/STRT_MEAS") (class "Default")
      (node (ref "R12") (pin "2") (pinfunction "2_2") (pintype "passive"))
      (node (ref "T1") (pin "1") (pinfunction "G_1") (pintype "passive"))
      (node (ref "U2") (pin "11") (pinfunction "PB5_11") (pintype "bidirectional"))
    )
    (net (code "16") (name "/SWCLK") (class "Default")
      (node (ref "J4") (pin "3") (pinfunction "3_3") (pintype "bidirectional"))
      (node (ref "U2") (pin "4") (pinfunction "PA14_4") (pintype "bidirectional"))
    )
    (net (code "17") (name "/SWDIO") (class "Default")
      (node (ref "J4") (pin "2") (pinfunction "2_2") (pintype "bidirectional"))
      (node (ref "U2") (pin "3") (pinfunction "PA13_3") (pintype "input"))
    )
    (net (code "18") (name "/TIM1CH2") (class "Default")
      (node (ref "J4") (pin "7") (pinfunction "7_7") (pintype "bidirectional"))
      (node (ref "U2") (pin "21") (pinfunction "PA9_21") (pintype "bidirectional"))
    )
    (net (code "19") (name "/U1_RX") (class "Default")
      (node (ref "J5") (pin "4") (pinfunction "4_4") (pintype "bidirectional"))
      (node (ref "U2") (pin "9") (pinfunction "PB7_9") (pintype "bidirectional"))
    )
    (net (code "20") (name "/U1_TX") (class "Default")
      (node (ref "J5") (pin "5") (pinfunction "5_5") (pintype "bidirectional"))
      (node (ref "U2") (pin "10") (pinfunction "PB6_10") (pintype "bidirectional"))
    )
    (net (code "21") (name "3.3V") (class "Default")
      (node (ref "C1") (pin "2") (pinfunction "2_2") (pintype "passive"))
      (node (ref "C11") (pin "2") (pinfunction "2_2") (pintype "passive"))
      (node (ref "C16") (pin "2") (pinfunction "2_2") (pintype "passive"))
      (node (ref "C2") (pin "2") (pinfunction "2_2") (pintype "passive"))
      (node (ref "C20") (pin "2") (pinfunction "2_2") (pintype "passive"))
      (node (ref "IC1") (pin "8") (pinfunction "Vcc_8") (pintype "power_in"))
      (node (ref "J3") (pin "1") (pinfunction "1_1") (pintype "bidirectional"))
      (node (ref "J4") (pin "1") (pinfunction "1_1") (pintype "bidirectional"))
      (node (ref "J5") (pin "2") (pinfunction "2_2") (pintype "bidirectional"))
      (node (ref "J6") (pin "1") (pinfunction "1_1") (pintype "bidirectional"))
      (node (ref "R10") (pin "2") (pinfunction "2_2") (pintype "passive"))
      (node (ref "R13") (pin "2") (pinfunction "2_2") (pintype "passive"))
      (node (ref "R18") (pin "2") (pinfunction "2_2") (pintype "passive"))
      (node (ref "R19") (pin "2") (pinfunction "2_2") (pintype "passive"))
      (node (ref "R26") (pin "2") (pinfunction "2_2") (pintype "passive"))
      (node (ref "R27") (pin "2") (pinfunction "2_2") (pintype "passive"))
      (node (ref "R29") (pin "2") (pinfunction "2_2") (pintype "passive"))
      (node (ref "R30") (pin "2") (pinfunction "2_2") (pintype "passive"))
      (node (ref "U1") (pin "5") (pinfunction "V+_5") (pintype "power_in"))
      (node (ref "U2") (pin "1") (pinfunction "VCC_1") (pintype "power_in"))
      (node (ref "U3") (pin "12") (pinfunction "LDO2_12") (pintype "output"))
      (node (ref "U4") (pin "5") (pinfunction "V+_5") (pintype "power_in"))
    )
    (net (code "22") (name "GND") (class "Default")
      (node (ref "C1") (pin "1") (pinfunction "1_1") (pintype "passive"))
      (node (ref "C10") (pin "1") (pinfunction "1_1") (pintype "passive"))
      (node (ref "C11") (pin "1") (pinfunction "1_1") (pintype "passive"))
      (node (ref "C12") (pin "2") (pinfunction "2_2") (pintype "passive"))
      (node (ref "C13") (pin "1") (pinfunction "1_1") (pintype "passive"))
      (node (ref "C14") (pin "1") (pinfunction "1_1") (pintype "passive"))
      (node (ref "C15") (pin "1") (pinfunction "1_1") (pintype "passive"))
      (node (ref "C16") (pin "1") (pinfunction "1_1") (pintype "passive"))
      (node (ref "C18") (pin "1") (pinfunction "1_1") (pintype "passive"))
      (node (ref "C19") (pin "1") (pinfunction "1_1") (pintype "passive"))
      (node (ref "C2") (pin "1") (pinfunction "1_1") (pintype "passive"))
      (node (ref "C20") (pin "1") (pinfunction "1_1") (pintype "passive"))
      (node (ref "C3") (pin "1") (pinfunction "1_1") (pintype "passive"))
      (node (ref "C4") (pin "1") (pinfunction "1_1") (pintype "passive"))
      (node (ref "C5") (pin "1") (pinfunction "1_1") (pintype "passive"))
      (node (ref "C6") (pin "2") (pinfunction "2_2") (pintype "passive"))
      (node (ref "C7") (pin "1") (pinfunction "1_1") (pintype "passive"))
      (node (ref "C8") (pin "1") (pinfunction "1_1") (pintype "passive"))
      (node (ref "C9") (pin "1") (pinfunction "1_1") (pintype "passive"))
      (node (ref "GND") (pin "1") (pinfunction "1_1") (pintype "bidirectional"))
      (node (ref "GND_NTC1") (pin "1") (pinfunction "1_1") (pintype "bidirectional"))
      (node (ref "GND_NTC2") (pin "1") (pinfunction "1_1") (pintype "bidirectional"))
      (node (ref "IC1") (pin "4") (pinfunction "GND_4") (pintype "power_in"))
      (node (ref "J1") (pin "2") (pinfunction "2_2") (pintype "passive"))
      (node (ref "J1") (pin "3") (pinfunction "3_3") (pintype "passive"))
      (node (ref "J1") (pin "4") (pinfunction "4_4") (pintype "passive"))
      (node (ref "J1") (pin "5") (pinfunction "5_5") (pintype "passive"))
      (node (ref "J2") (pin "2") (pinfunction "2_2") (pintype "passive"))
      (node (ref "J2") (pin "3") (pinfunction "3_3") (pintype "passive"))
      (node (ref "J2") (pin "4") (pinfunction "4_4") (pintype "passive"))
      (node (ref "J3") (pin "3") (pinfunction "3_3") (pintype "bidirectional"))
      (node (ref "J4") (pin "4") (pinfunction "4_4") (pintype "bidirectional"))
      (node (ref "J4") (pin "6") (pinfunction "6_6") (pintype "bidirectional"))
      (node (ref "J5") (pin "3") (pinfunction "3_3") (pintype "bidirectional"))
      (node (ref "J6") (pin "2") (pinfunction "2_2") (pintype "bidirectional"))
      (node (ref "R11") (pin "1") (pinfunction "1_1") (pintype "passive"))
      (node (ref "R12") (pin "1") (pinfunction "1_1") (pintype "passive"))
      (node (ref "R15") (pin "1") (pinfunction "1_1") (pintype "passive"))
      (node (ref "R24") (pin "1") (pinfunction "1_1") (pintype "passive"))
      (node (ref "R28") (pin "1") (pinfunction "1_1") (pintype "passive"))
      (node (ref "R33") (pin "1") (pinfunction "1_1") (pintype "passive"))
      (node (ref "R35") (pin "1") (pinfunction "1_1") (pintype "passive"))
      (node (ref "R39") (pin "1") (pinfunction "1_1") (pintype "passive"))
      (node (ref "T1") (pin "2") (pinfunction "S_2") (pintype "passive"))
      (node (ref "U1") (pin "2") (pinfunction "V-_2") (pintype "power_in"))
      (node (ref "U2") (pin "14") (pinfunction "GND_14") (pintype "power_in"))
      (node (ref "U2") (pin "16") (pinfunction "GND_16") (pintype "power_in"))
      (node (ref "U2") (pin "2") (pinfunction "GND_2") (pintype "power_in"))
      (node (ref "U2") (pin "22") (pinfunction "GND_22") (pintype "power_in"))
      (node (ref "U3") (pin "13") (pinfunction "CONF_13") (pintype "input"))
      (node (ref "U3") (pin "18") (pinfunction "PGND_18") (pintype "power_in"))
      (node (ref "U3") (pin "21") (pinfunction "EXP_21") (pintype "power_in"))
      (node (ref "U3") (pin "4") (pinfunction "GND_4") (pintype "power_in"))
      (node (ref "U3") (pin "6") (pinfunction "LDO2_EN_6") (pintype "input"))
      (node (ref "U4") (pin "2") (pinfunction "V-_2") (pintype "power_in"))
    )
    (net (code "23") (name "Net-(C5-Pad2)") (class "Default")
      (node (ref "C5") (pin "2") (pinfunction "2_2") (pintype "passive"))
      (node (ref "R14") (pin "1") (pinfunction "1_1") (pintype "passive"))
      (node (ref "R16") (pin "2") (pinfunction "2_2") (pintype "passive"))
      (node (ref "R17") (pin "1") (pinfunction "1_1") (pintype "passive"))
    )
    (net (code "24") (name "Net-(IC1-~{HOLD}{slash}~{RESET}(I{slash}03))") (class "Default")
      (node (ref "IC1") (pin "7") (pinfunction "~{HOLD}/~{RESET}(I/03)_7") (pintype "bidirectional"))
      (node (ref "R29") (pin "1") (pinfunction "1_1") (pintype "passive"))
    )
    (net (code "25") (name "Net-(IC1-~{WP}(I{slash}O2))") (class "Default")
      (node (ref "IC1") (pin "3") (pinfunction "~{WP}(I/O2)_3") (pintype "bidirectional"))
      (node (ref "R30") (pin "1") (pinfunction "1_1") (pintype "passive"))
    )
    (net (code "26") (name "Net-(J1-Pad1)") (class "Default")
      (node (ref "J1") (pin "1") (pinfunction "1_1") (pintype "bidirectional"))
      (node (ref "R14") (pin "2") (pinfunction "2_2") (pintype "passive"))
    )
    (net (code "27") (name "Net-(J2-Pad1)") (class "Default")
      (node (ref "J2") (pin "1") (pinfunction "1_1") (pintype "bidirectional"))
      (node (ref "R17") (pin "2") (pinfunction "2_2") (pintype "passive"))
    )
    (net (code "28") (name "Net-(T1-D)") (class "Default")
      (node (ref "R2") (pin "1") (pinfunction "1_1") (pintype "passive"))
      (node (ref "R3") (pin "2") (pinfunction "2_2") (pintype "passive"))
      (node (ref "R4") (pin "2") (pinfunction "2_2") (pintype "passive"))
      (node (ref "R5") (pin "2") (pinfunction "2_2") (pintype "passive"))
      (node (ref "R6") (pin "2") (pinfunction "2_2") (pintype "passive"))
      (node (ref "R7") (pin "2") (pinfunction "2_2") (pintype "passive"))
      (node (ref "R8") (pin "2") (pinfunction "2_2") (pintype "passive"))
      (node (ref "T1") (pin "3") (pinfunction "D_3") (pintype "passive"))
    )
    (net (code "29") (name "Net-(T2-D)") (class "Default")
      (node (ref "IN") (pin "1") (pinfunction "1_1") (pintype "bidirectional"))
      (node (ref "R3") (pin "1") (pinfunction "1_1") (pintype "passive"))
      (node (ref "R4") (pin "1") (pinfunction "1_1") (pintype "passive"))
      (node (ref "R5") (pin "1") (pinfunction "1_1") (pintype "passive"))
      (node (ref "R6") (pin "1") (pinfunction "1_1") (pintype "passive"))
      (node (ref "R7") (pin "1") (pinfunction "1_1") (pintype "passive"))
      (node (ref "R8") (pin "1") (pinfunction "1_1") (pintype "passive"))
      (node (ref "R9") (pin "1") (pinfunction "1_1") (pintype "passive"))
      (node (ref "T2") (pin "3") (pinfunction "D_3") (pintype "passive"))
    )
    (net (code "30") (name "Net-(T2-G)") (class "Default")
      (node (ref "R21") (pin "1") (pinfunction "1_1") (pintype "passive"))
      (node (ref "R24") (pin "2") (pinfunction "2_2") (pintype "passive"))
      (node (ref "T2") (pin "1") (pinfunction "G_1") (pintype "passive"))
    )
    (net (code "31") (name "Net-(T2-S)") (class "Default")
      (node (ref "C7") (pin "2") (pinfunction "2_2") (pintype "passive"))
      (node (ref "C8") (pin "2") (pinfunction "2_2") (pintype "passive"))
      (node (ref "C9") (pin "2") (pinfunction "2_2") (pintype "passive"))
      (node (ref "R21") (pin "2") (pinfunction "2_2") (pintype "passive"))
      (node (ref "R22") (pin "2") (pinfunction "2_2") (pintype "passive"))
      (node (ref "T2") (pin "2") (pinfunction "S_2") (pintype "passive"))
      (node (ref "U3") (pin "20") (pinfunction "IN_HV_20") (pintype "input"))
    )
    (net (code "32") (name "Net-(U1-+IN)") (class "Default")
      (node (ref "R11") (pin "2") (pinfunction "2_2") (pintype "passive"))
      (node (ref "R9") (pin "2") (pinfunction "2_2") (pintype "passive"))
      (node (ref "U1") (pin "3") (pinfunction "+IN_3") (pintype "input"))
    )
    (net (code "33") (name "Net-(U1--IN)") (class "Default")
      (node (ref "R1") (pin "1") (pinfunction "1_1") (pintype "passive"))
      (node (ref "R2") (pin "2") (pinfunction "2_2") (pintype "passive"))
      (node (ref "U1") (pin "4") (pinfunction "-IN_4") (pintype "input"))
    )
    (net (code "34") (name "Net-(U2-RFIO)") (class "Default")
      (node (ref "C4") (pin "2") (pinfunction "2_2") (pintype "passive"))
      (node (ref "R16") (pin "1") (pinfunction "1_1") (pintype "passive"))
      (node (ref "U2") (pin "15") (pinfunction "RFIO_15") (pintype "passive"))
    )
    (net (code "35") (name "Net-(U2-RST)") (class "Default")
      (node (ref "C3") (pin "2") (pinfunction "2_2") (pintype "passive"))
      (node (ref "R10") (pin "1") (pinfunction "1_1") (pintype "passive"))
      (node (ref "U2") (pin "17") (pinfunction "RST_17") (pintype "passive"))
    )
    (net (code "36") (name "Net-(U3-BATT)") (class "Default")
      (node (ref "C12") (pin "1") (pinfunction "1_1") (pintype "passive"))
      (node (ref "U3") (pin "14") (pinfunction "BATT_14") (pintype "bidirectional"))
    )
    (net (code "37") (name "Net-(U3-BATT_CHG)") (class "Default")
      (node (ref "R19") (pin "1") (pinfunction "1_1") (pintype "passive"))
      (node (ref "R20") (pin "1") (pinfunction "1_1") (pintype "passive"))
      (node (ref "U3") (pin "7") (pinfunction "BATT_CHG_7") (pintype "output"))
    )
    (net (code "38") (name "Net-(U3-BATT_CONN)") (class "Default")
      (node (ref "R18") (pin "1") (pinfunction "1_1") (pintype "passive"))
      (node (ref "R23") (pin "1") (pinfunction "1_1") (pintype "passive"))
      (node (ref "U3") (pin "8") (pinfunction "BATT_CONN_8") (pintype "output"))
    )
    (net (code "39") (name "Net-(U3-EOC)") (class "Default")
      (node (ref "R32") (pin "1") (pinfunction "1_1") (pintype "passive"))
      (node (ref "R33") (pin "2") (pinfunction "2_2") (pintype "passive"))
      (node (ref "U3") (pin "9") (pinfunction "EOC_9") (pintype "input"))
    )
    (net (code "40") (name "Net-(U3-IN_LV)") (class "Default")
      (node (ref "L1") (pin "2") (pinfunction "2_2") (pintype "passive"))
      (node (ref "U3") (pin "16") (pinfunction "IN_LV_16") (pintype "input"))
    )
    (net (code "41") (name "Net-(U3-LDO1)") (class "Default")
      (node (ref "C10") (pin "2") (pinfunction "2_2") (pintype "passive"))
      (node (ref "U3") (pin "11") (pinfunction "LDO1_11") (pintype "output"))
    )
    (net (code "42") (name "Net-(U3-LDO1_EN)") (class "Default")
      (node (ref "R13") (pin "1") (pinfunction "1_1") (pintype "passive"))
      (node (ref "R15") (pin "2") (pinfunction "2_2") (pintype "passive"))
      (node (ref "U3") (pin "5") (pinfunction "LDO1_EN_5") (pintype "input"))
    )
    (net (code "43") (name "Net-(U3-L_HV)") (class "Default")
      (node (ref "L1") (pin "1") (pinfunction "1_1") (pintype "passive"))
      (node (ref "U3") (pin "19") (pinfunction "L_HV_19") (pintype "input"))
    )
    (net (code "44") (name "Net-(U3-MPP)") (class "Default")
      (node (ref "R22") (pin "1") (pinfunction "1_1") (pintype "passive"))
      (node (ref "R25") (pin "2") (pinfunction "2_2") (pintype "passive"))
      (node (ref "U3") (pin "1") (pinfunction "MPP_1") (pintype "input"))
    )
    (net (code "45") (name "Net-(U3-MPP_REF)") (class "Default")
      (node (ref "C6") (pin "1") (pinfunction "1_1") (pintype "passive"))
      (node (ref "U3") (pin "3") (pinfunction "MPP_REF_3") (pintype "input"))
    )
    (net (code "46") (name "Net-(U3-MPP_SET)") (class "Default")
      (node (ref "R25") (pin "1") (pinfunction "1_1") (pintype "passive"))
      (node (ref "R28") (pin "2") (pinfunction "2_2") (pintype "passive"))
      (node (ref "U3") (pin "2") (pinfunction "MPP_SET_2") (pintype "input"))
    )
    (net (code "47") (name "Net-(U3-STORE)") (class "Default")
      (node (ref "C13") (pin "2") (pinfunction "2_2") (pintype "passive"))
      (node (ref "C14") (pin "2") (pinfunction "2_2") (pintype "passive"))
      (node (ref "C15") (pin "2") (pinfunction "2_2") (pintype "passive"))
      (node (ref "R31") (pin "2") (pinfunction "2_2") (pintype "passive"))
      (node (ref "U3") (pin "15") (pinfunction "STORE_15") (pintype "bidirectional"))
    )
    (net (code "48") (name "Net-(U3-UVP)") (class "Default")
      (node (ref "R31") (pin "1") (pinfunction "1_1") (pintype "passive"))
      (node (ref "R32") (pin "2") (pinfunction "2_2") (pintype "passive"))
      (node (ref "U3") (pin "10") (pinfunction "UVP_10") (pintype "input"))
    )
    (net (code "49") (name "Net-(U4-+IN)") (class "Default")
      (node (ref "R34") (pin "1") (pinfunction "1_1") (pintype "passive"))
      (node (ref "R35") (pin "2") (pinfunction "2_2") (pintype "passive"))
      (node (ref "U4") (pin "3") (pinfunction "+IN_3") (pintype "input"))
    )
    (net (code "50") (name "Net-(U4--IN)") (class "Default")
      (node (ref "C17") (pin "1") (pinfunction "1_1") (pintype "passive"))
      (node (ref "R38") (pin "1") (pinfunction "1_1") (pintype "passive"))
      (node (ref "R39") (pin "2") (pinfunction "2_2") (pintype "passive"))
      (node (ref "U4") (pin "4") (pinfunction "-IN_4") (pintype "input"))
    )
    (net (code "51") (name "Net-(U4-OUT)") (class "Default")
      (node (ref "C17") (pin "2") (pinfunction "2_2") (pintype "passive"))
      (node (ref "R36") (pin "2") (pinfunction "2_2") (pintype "passive"))
      (node (ref "R37") (pin "2") (pinfunction "2_2") (pintype "passive"))
      (node (ref "R38") (pin "2") (pinfunction "2_2") (pintype "passive"))
      (node (ref "U4") (pin "1") (pinfunction "OUT_1") (pintype "output"))
    )
    (net (code "52") (name "unconnected-(J5-Pad1)") (class "Default")
      (node (ref "J5") (pin "1") (pinfunction "1_1") (pintype "bidirectional+no_connect"))
    )
    (net (code "53") (name "unconnected-(U2-PB0-Pad28)") (class "Default")
      (node (ref "U2") (pin "28") (pinfunction "PB0_28") (pintype "bidirectional+no_connect"))
    )
    (net (code "54") (name "unconnected-(U3-NC-Pad17)") (class "Default")
      (node (ref "U3") (pin "17") (pinfunction "NC_17") (pintype "passive"))
    )
  )
)
